# SparkFun_RTK_Facet_-_Display_SD_SIM.net
KiCad netlist of a schematic drawn in EAGLE
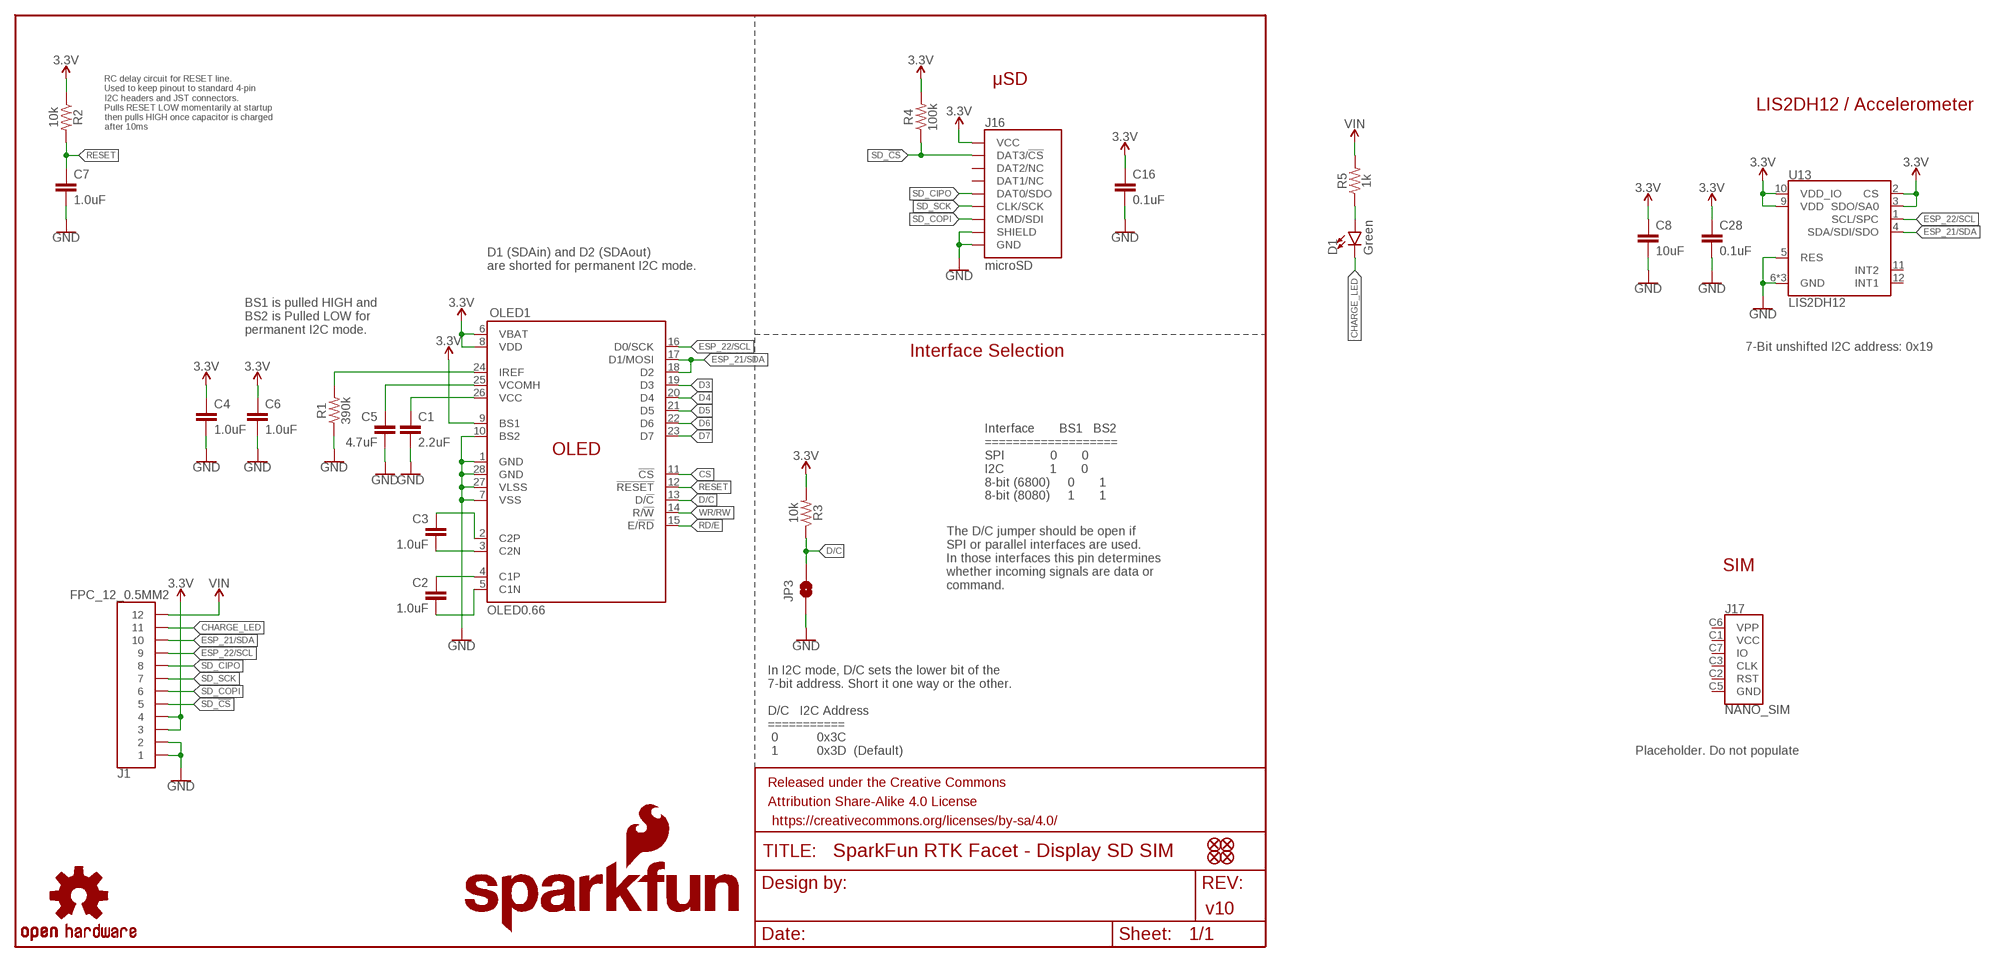
[diagram p0: schematic, sheet 1]

(export (version "E")
  (design (tool "Eeschema 10.0.6"))
  (components
    (comp (ref "C1")
      (value "2.2uF")
      (footprint "eagle-import:0805")
      (libsource (lib "eagle-import") (part "2.2UF-0805-25V-(+80/-20%)"))
    )
    (comp (ref "C2")
      (value "1.0uF")
      (footprint "eagle-import:0805")
      (libsource (lib "eagle-import") (part "1.0UF-0805-25V-10%"))
    )
    (comp (ref "C3")
      (value "1.0uF")
      (footprint "eagle-import:0805")
      (libsource (lib "eagle-import") (part "1.0UF-0805-25V-10%"))
    )
    (comp (ref "C4")
      (value "1.0uF")
      (footprint "eagle-import:0603")
      (libsource (lib "eagle-import") (part "1.0UF-0603-16V-10%"))
    )
    (comp (ref "C5")
      (value "4.7uF")
      (footprint "eagle-import:1206")
      (libsource (lib "eagle-import") (part "4.7UF-1206-16V-(+80/-20%)"))
    )
    (comp (ref "C6")
      (value "1.0uF")
      (footprint "eagle-import:0603")
      (libsource (lib "eagle-import") (part "1.0UF-0603-16V-10%"))
    )
    (comp (ref "C7")
      (value "1.0uF")
      (footprint "eagle-import:0603")
      (libsource (lib "eagle-import") (part "1.0UF-0603-16V-10%"))
    )
    (comp (ref "C8")
      (value "10uF")
      (footprint "eagle-import:0603")
      (libsource (lib "eagle-import") (part "10UF-0603-6.3V-20%"))
    )
    (comp (ref "C16")
      (value "0.1uF")
      (footprint "eagle-import:0603")
      (libsource (lib "eagle-import") (part "0.1UF-0603-25V-(+80/-20%)"))
    )
    (comp (ref "C28")
      (value "0.1uF")
      (footprint "eagle-import:0603")
      (libsource (lib "eagle-import") (part "0.1UF-0603-25V-(+80/-20%)"))
    )
    (comp (ref "D1")
      (value "Green")
      (footprint "eagle-import:LED-1206-BOTTOM")
      (libsource (lib "eagle-import") (part "LED-GREEN1206-BOTTOM"))
    )
    (comp (ref "FID1")
      (value "FIDUCIAL1X2")
      (footprint "eagle-import:FIDUCIAL-1X2")
      (libsource (lib "eagle-import") (part "FIDUCIAL1X2"))
    )
    (comp (ref "FID2")
      (value "FIDUCIAL1X2")
      (footprint "eagle-import:FIDUCIAL-1X2")
      (libsource (lib "eagle-import") (part "FIDUCIAL1X2"))
    )
    (comp (ref "FID3")
      (value "FIDUCIAL1X2")
      (footprint "eagle-import:FIDUCIAL-1X2")
      (libsource (lib "eagle-import") (part "FIDUCIAL1X2"))
    )
    (comp (ref "FID4")
      (value "FIDUCIAL1X2")
      (footprint "eagle-import:FIDUCIAL-1X2")
      (libsource (lib "eagle-import") (part "FIDUCIAL1X2"))
    )
    (comp (ref "FRAME1")
      (value "FRAME-LETTER")
      (footprint "eagle-import:CREATIVE_COMMONS")
      (libsource (lib "eagle-import") (part "FRAME-LETTER"))
    )
    (comp (ref "J1")
      (value "FPC_12_0.5MM2")
      (footprint "eagle-import:FPC_12_FLIP_DOUBLESIDED_2")
      (libsource (lib "eagle-import") (part "FPC_12_0.5MM2"))
    )
    (comp (ref "J16")
      (value "microSD")
      (footprint "eagle-import:MICRO-SD-SOCKET")
      (libsource (lib "eagle-import") (part "MICRO-SD-SDIOPUSH-PUSH"))
    )
    (comp (ref "J17")
      (value "NANO_SIM")
      (footprint "eagle-import:NANO_SIM_WURTH_693043020611")
      (libsource (lib "eagle-import") (part "NANO_SIMWURTH"))
    )
    (comp (ref "JP3")
      (value "JUMPER-SMT_2_NO_SILK")
      (footprint "eagle-import:SMT-JUMPER_2_NO_SILK")
      (libsource (lib "eagle-import") (part "JUMPER-SMT_2_NO_SILK"))
    )
    (comp (ref "LOGO3")
      (value "OSHW-LOGOS")
      (footprint "eagle-import:OSHW-LOGO-S")
      (libsource (lib "eagle-import") (part "OSHW-LOGOS"))
    )
    (comp (ref "LOGO5")
      (value "SFE_LOGO_NAME_FLAME.1_INCH")
      (footprint "eagle-import:SFE_LOGO_NAME_FLAME_.1")
      (libsource (lib "eagle-import") (part "SFE_LOGO_NAME_FLAME.1_INCH"))
    )
    (comp (ref "OLED1")
      (value "OLED0.66")
      (footprint "eagle-import:OLED-0.66-64X48")
      (libsource (lib "eagle-import") (part "OLED0.66"))
    )
    (comp (ref "R1")
      (value "390k")
      (footprint "eagle-import:0603")
      (libsource (lib "eagle-import") (part "390KOHM-0603-1/10W-1%"))
    )
    (comp (ref "R2")
      (value "10k")
      (footprint "eagle-import:0603")
      (libsource (lib "eagle-import") (part "10KOHM-0603-1/10W-1%"))
    )
    (comp (ref "R3")
      (value "10k")
      (footprint "eagle-import:0603")
      (libsource (lib "eagle-import") (part "10KOHM-0603-1/10W-1%"))
    )
    (comp (ref "R4")
      (value "100k")
      (footprint "eagle-import:0603")
      (libsource (lib "eagle-import") (part "100KOHM-0603-1/10W-1%"))
    )
    (comp (ref "R5")
      (value "1k")
      (footprint "eagle-import:0603")
      (libsource (lib "eagle-import") (part "1KOHM-0603-1/10W-1%"))
    )
    (comp (ref "U13")
      (value "LIS2DH12")
      (footprint "eagle-import:LGA-12-LISDH12")
      (libsource (lib "eagle-import") (part "LIS2DH12"))
    )
  )
  (nets
    (net (code "1") (name "/SD_~{CS}") (class "Default")
      (node (ref "J1") (pin "5") (pinfunction "5_5") (pintype "bidirectional"))
      (node (ref "J16") (pin "CS/DAT3") (pinfunction "DAT3/~{CS}_CS/DAT3") (pintype "bidirectional"))
      (node (ref "R4") (pin "1") (pinfunction "1_1") (pintype "passive"))
    )
    (net (code "2") (name "3.3V") (class "Default")
      (node (ref "C16") (pin "1") (pinfunction "1_1") (pintype "passive"))
      (node (ref "C28") (pin "1") (pinfunction "1_1") (pintype "passive"))
      (node (ref "C4") (pin "1") (pinfunction "1_1") (pintype "passive"))
      (node (ref "C6") (pin "1") (pinfunction "1_1") (pintype "passive"))
      (node (ref "C8") (pin "1") (pinfunction "1_1") (pintype "passive"))
      (node (ref "J1") (pin "3") (pinfunction "3_3") (pintype "bidirectional"))
      (node (ref "J1") (pin "4") (pinfunction "4_4") (pintype "bidirectional"))
      (node (ref "J16") (pin "VCC") (pinfunction "VCC_VCC") (pintype "bidirectional"))
      (node (ref "OLED1") (pin "6") (pinfunction "VBAT_6") (pintype "bidirectional"))
      (node (ref "OLED1") (pin "8") (pinfunction "VDD_8") (pintype "bidirectional"))
      (node (ref "OLED1") (pin "9") (pinfunction "BS1_9") (pintype "bidirectional"))
      (node (ref "R2") (pin "1") (pinfunction "1_1") (pintype "passive"))
      (node (ref "R3") (pin "2") (pinfunction "2_2") (pintype "passive"))
      (node (ref "R4") (pin "2") (pinfunction "2_2") (pintype "passive"))
      (node (ref "U13") (pin "10") (pinfunction "VDD_IO_10") (pintype "bidirectional"))
      (node (ref "U13") (pin "2") (pinfunction "CS_2") (pintype "bidirectional"))
      (node (ref "U13") (pin "3") (pinfunction "SDO/SA0_3") (pintype "bidirectional"))
      (node (ref "U13") (pin "9") (pinfunction "VDD_9") (pintype "bidirectional"))
    )
    (net (code "3") (name "CHARGE_LED") (class "Default")
      (node (ref "D1") (pin "C") (pinfunction "C_C") (pintype "passive"))
      (node (ref "J1") (pin "11") (pinfunction "11_11") (pintype "bidirectional"))
    )
    (net (code "4") (name "CS") (class "Default")
      (node (ref "OLED1") (pin "11") (pinfunction "~{CS}_11") (pintype "bidirectional"))
    )
    (net (code "5") (name "D3") (class "Default")
      (node (ref "OLED1") (pin "19") (pinfunction "D3_19") (pintype "bidirectional"))
    )
    (net (code "6") (name "D4") (class "Default")
      (node (ref "OLED1") (pin "20") (pinfunction "D4_20") (pintype "bidirectional"))
    )
    (net (code "7") (name "D5") (class "Default")
      (node (ref "OLED1") (pin "21") (pinfunction "D5_21") (pintype "bidirectional"))
    )
    (net (code "8") (name "D6") (class "Default")
      (node (ref "OLED1") (pin "22") (pinfunction "D6_22") (pintype "bidirectional"))
    )
    (net (code "9") (name "D7") (class "Default")
      (node (ref "OLED1") (pin "23") (pinfunction "D7_23") (pintype "bidirectional"))
    )
    (net (code "10") (name "D{slash}C") (class "Default")
      (node (ref "JP3") (pin "2") (pinfunction "2_2") (pintype "passive"))
      (node (ref "OLED1") (pin "13") (pinfunction "D/~{C}_13") (pintype "bidirectional"))
      (node (ref "R3") (pin "1") (pinfunction "1_1") (pintype "passive"))
    )
    (net (code "11") (name "ESP_21{slash}SDA") (class "Default")
      (node (ref "J1") (pin "10") (pinfunction "10_10") (pintype "bidirectional"))
      (node (ref "OLED1") (pin "17") (pinfunction "D1/MOSI_17") (pintype "bidirectional"))
      (node (ref "OLED1") (pin "18") (pinfunction "D2_18") (pintype "bidirectional"))
      (node (ref "U13") (pin "4") (pinfunction "SDA/SDI/SDO_4") (pintype "bidirectional"))
    )
    (net (code "12") (name "ESP_22{slash}SCL") (class "Default")
      (node (ref "J1") (pin "9") (pinfunction "9_9") (pintype "bidirectional"))
      (node (ref "OLED1") (pin "16") (pinfunction "D0/SCK_16") (pintype "bidirectional"))
      (node (ref "U13") (pin "1") (pinfunction "SCL/SPC_1") (pintype "bidirectional"))
    )
    (net (code "13") (name "GND") (class "Default")
      (node (ref "C1") (pin "2") (pinfunction "2_2") (pintype "passive"))
      (node (ref "C16") (pin "2") (pinfunction "2_2") (pintype "passive"))
      (node (ref "C28") (pin "2") (pinfunction "2_2") (pintype "passive"))
      (node (ref "C4") (pin "2") (pinfunction "2_2") (pintype "passive"))
      (node (ref "C5") (pin "2") (pinfunction "2_2") (pintype "passive"))
      (node (ref "C6") (pin "2") (pinfunction "2_2") (pintype "passive"))
      (node (ref "C7") (pin "2") (pinfunction "2_2") (pintype "passive"))
      (node (ref "C8") (pin "2") (pinfunction "2_2") (pintype "passive"))
      (node (ref "J1") (pin "1") (pinfunction "1_1") (pintype "bidirectional"))
      (node (ref "J1") (pin "2") (pinfunction "2_2") (pintype "bidirectional"))
      (node (ref "J16") (pin "CD1") (pinfunction "SHIELD_CD1") (pintype "bidirectional"))
      (node (ref "J16") (pin "GND") (pinfunction "GND_GND") (pintype "bidirectional"))
      (node (ref "J16") (pin "GND1") (pinfunction "GND_GND1") (pintype "bidirectional"))
      (node (ref "J16") (pin "GND3") (pinfunction "GND_GND3") (pintype "bidirectional"))
      (node (ref "JP3") (pin "1") (pinfunction "1_1") (pintype "passive"))
      (node (ref "OLED1") (pin "1") (pinfunction "GND_1") (pintype "bidirectional"))
      (node (ref "OLED1") (pin "10") (pinfunction "BS2_10") (pintype "bidirectional"))
      (node (ref "OLED1") (pin "27") (pinfunction "VLSS_27") (pintype "bidirectional"))
      (node (ref "OLED1") (pin "28") (pinfunction "GND_28") (pintype "bidirectional"))
      (node (ref "OLED1") (pin "7") (pinfunction "VSS_7") (pintype "bidirectional"))
      (node (ref "R1") (pin "1") (pinfunction "1_1") (pintype "passive"))
      (node (ref "U13") (pin "5") (pinfunction "RES_5") (pintype "bidirectional"))
      (node (ref "U13") (pin "6") (pinfunction "GND_6") (pintype "bidirectional"))
      (node (ref "U13") (pin "7") (pinfunction "GND_7") (pintype "bidirectional"))
      (node (ref "U13") (pin "8") (pinfunction "GND_8") (pintype "bidirectional"))
    )
    (net (code "14") (name "Net-(D1-PadA)") (class "Default")
      (node (ref "D1") (pin "A") (pinfunction "A_A") (pintype "passive"))
      (node (ref "R5") (pin "1") (pinfunction "1_1") (pintype "passive"))
    )
    (net (code "15") (name "Net-(OLED1-C1N)") (class "Default")
      (node (ref "C2") (pin "2") (pinfunction "2_2") (pintype "passive"))
      (node (ref "OLED1") (pin "5") (pinfunction "C1N_5") (pintype "bidirectional"))
    )
    (net (code "16") (name "Net-(OLED1-C1P)") (class "Default")
      (node (ref "C2") (pin "1") (pinfunction "1_1") (pintype "passive"))
      (node (ref "OLED1") (pin "4") (pinfunction "C1P_4") (pintype "bidirectional"))
    )
    (net (code "17") (name "Net-(OLED1-C2N)") (class "Default")
      (node (ref "C3") (pin "2") (pinfunction "2_2") (pintype "passive"))
      (node (ref "OLED1") (pin "3") (pinfunction "C2N_3") (pintype "bidirectional"))
    )
    (net (code "18") (name "Net-(OLED1-C2P)") (class "Default")
      (node (ref "C3") (pin "1") (pinfunction "1_1") (pintype "passive"))
      (node (ref "OLED1") (pin "2") (pinfunction "C2P_2") (pintype "bidirectional"))
    )
    (net (code "19") (name "Net-(OLED1-IREF)") (class "Default")
      (node (ref "OLED1") (pin "24") (pinfunction "IREF_24") (pintype "bidirectional"))
      (node (ref "R1") (pin "2") (pinfunction "2_2") (pintype "passive"))
    )
    (net (code "20") (name "Net-(OLED1-VCC)") (class "Default")
      (node (ref "C1") (pin "1") (pinfunction "1_1") (pintype "passive"))
      (node (ref "OLED1") (pin "26") (pinfunction "VCC_26") (pintype "bidirectional"))
    )
    (net (code "21") (name "Net-(OLED1-VCOMH)") (class "Default")
      (node (ref "C5") (pin "1") (pinfunction "1_1") (pintype "passive"))
      (node (ref "OLED1") (pin "25") (pinfunction "VCOMH_25") (pintype "bidirectional"))
    )
    (net (code "22") (name "RD{slash}E") (class "Default")
      (node (ref "OLED1") (pin "15") (pinfunction "E/~{RD}_15") (pintype "bidirectional"))
    )
    (net (code "23") (name "RESET") (class "Default")
      (node (ref "C7") (pin "1") (pinfunction "1_1") (pintype "passive"))
      (node (ref "OLED1") (pin "12") (pinfunction "~{RESET}_12") (pintype "bidirectional"))
      (node (ref "R2") (pin "2") (pinfunction "2_2") (pintype "passive"))
    )
    (net (code "24") (name "SD_CIPO") (class "Default")
      (node (ref "J1") (pin "8") (pinfunction "8_8") (pintype "bidirectional"))
      (node (ref "J16") (pin "DO/DAT0") (pinfunction "DAT0/SDO_DO/DAT0") (pintype "bidirectional"))
    )
    (net (code "25") (name "SD_COPI") (class "Default")
      (node (ref "J1") (pin "6") (pinfunction "6_6") (pintype "bidirectional"))
      (node (ref "J16") (pin "DI/CMD") (pinfunction "CMD/SDI_DI/CMD") (pintype "bidirectional"))
    )
    (net (code "26") (name "SD_SCK") (class "Default")
      (node (ref "J1") (pin "7") (pinfunction "7_7") (pintype "bidirectional"))
      (node (ref "J16") (pin "SCLK") (pinfunction "CLK/SCK_SCLK") (pintype "bidirectional"))
    )
    (net (code "27") (name "VIN") (class "Default")
      (node (ref "J1") (pin "12") (pinfunction "12_12") (pintype "bidirectional"))
      (node (ref "R5") (pin "2") (pinfunction "2_2") (pintype "passive"))
    )
    (net (code "28") (name "WR{slash}RW") (class "Default")
      (node (ref "OLED1") (pin "14") (pinfunction "R/~{W}_14") (pintype "bidirectional"))
    )
    (net (code "29") (name "unconnected-(J16-DAT1{slash}NC-PadDAT1)") (class "Default")
      (node (ref "J16") (pin "DAT1") (pinfunction "DAT1/NC_DAT1") (pintype "bidirectional"))
    )
    (net (code "30") (name "unconnected-(J16-DAT2{slash}NC-PadDAT2)") (class "Default")
      (node (ref "J16") (pin "DAT2") (pinfunction "DAT2/NC_DAT2") (pintype "bidirectional"))
    )
    (net (code "31") (name "unconnected-(J17-CLK-PadC3)") (class "Default")
      (node (ref "J17") (pin "C3") (pinfunction "CLK_C3") (pintype "bidirectional"))
    )
    (net (code "32") (name "unconnected-(J17-GND-PadC5)") (class "Default")
      (node (ref "J17") (pin "C5") (pinfunction "GND_C5") (pintype "bidirectional"))
    )
    (net (code "33") (name "unconnected-(J17-IO-PadC7)") (class "Default")
      (node (ref "J17") (pin "C7") (pinfunction "IO_C7") (pintype "bidirectional"))
    )
    (net (code "34") (name "unconnected-(J17-RST-PadC2)") (class "Default")
      (node (ref "J17") (pin "C2") (pinfunction "RST_C2") (pintype "bidirectional"))
    )
    (net (code "35") (name "unconnected-(J17-VCC-PadC1)") (class "Default")
      (node (ref "J17") (pin "C1") (pinfunction "VCC_C1") (pintype "bidirectional"))
    )
    (net (code "36") (name "unconnected-(J17-VPP-PadC6)") (class "Default")
      (node (ref "J17") (pin "C6") (pinfunction "VPP_C6") (pintype "bidirectional"))
    )
    (net (code "37") (name "unconnected-(U13-INT1-Pad12)") (class "Default")
      (node (ref "U13") (pin "12") (pinfunction "INT1_12") (pintype "bidirectional"))
    )
    (net (code "38") (name "unconnected-(U13-INT2-Pad11)") (class "Default")
      (node (ref "U13") (pin "11") (pinfunction "INT2_11") (pintype "bidirectional"))
    )
  )
)
